# boardPower.net
KiCad netlist of a schematic drawn in Altium Designer
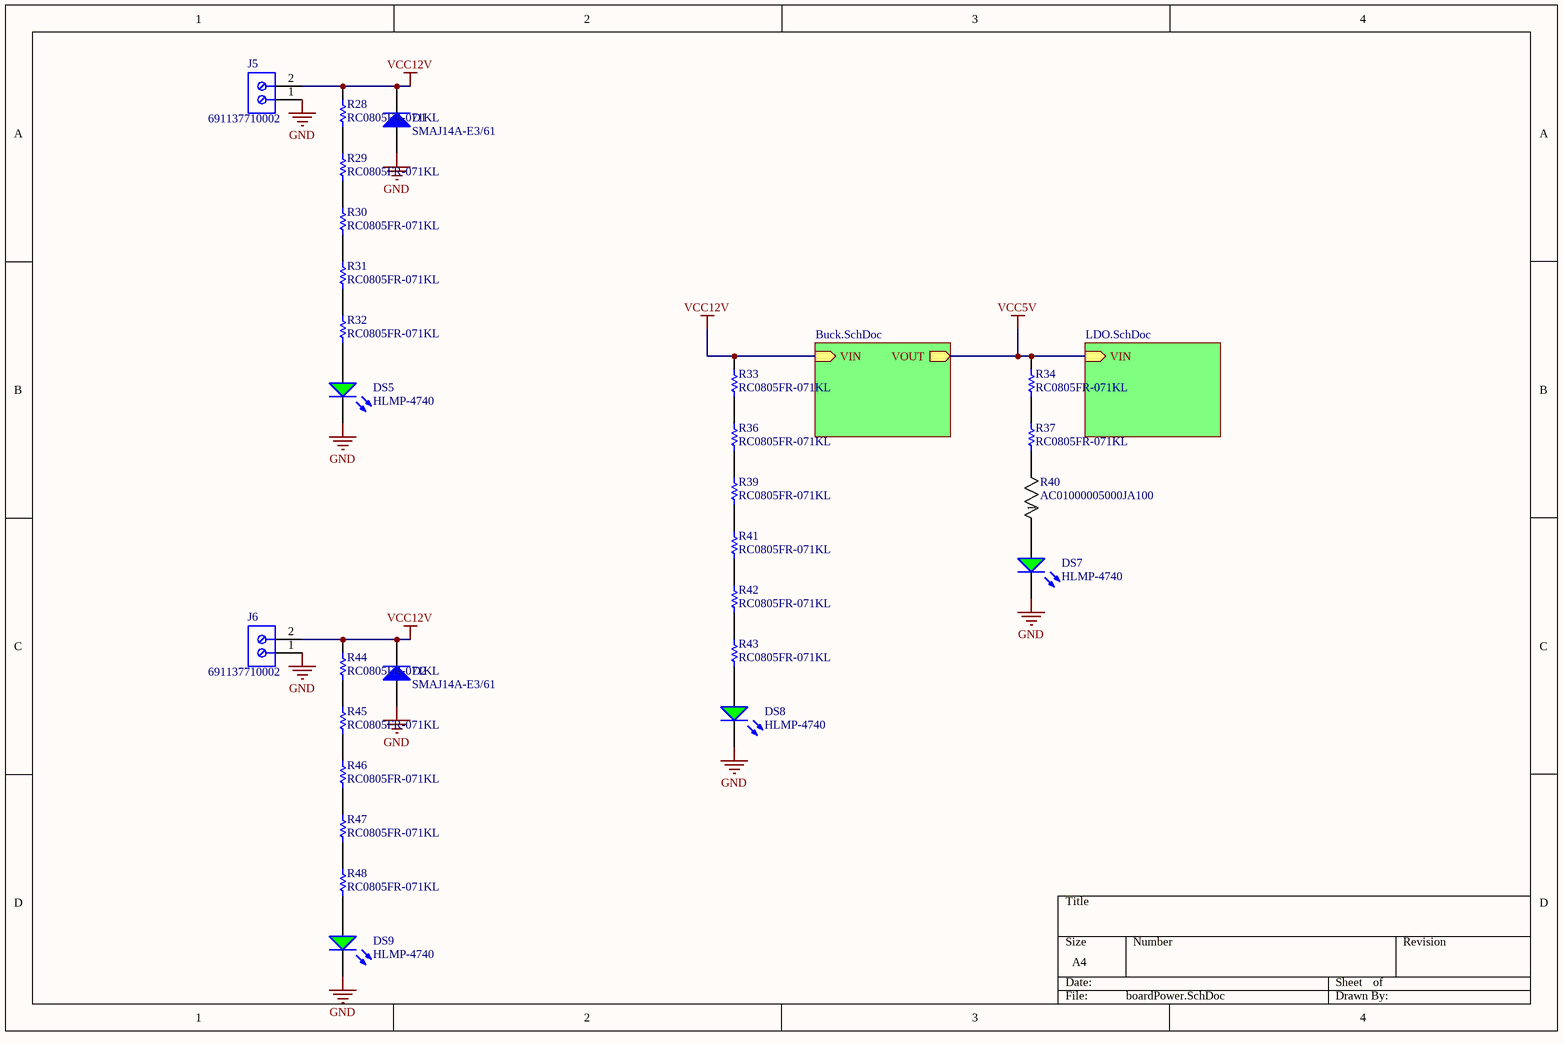
[diagram p0: boardPower.SchDoc]

(export (version "E")
  (design (tool "Eeschema 10.0.6"))
  (components
    (comp (ref "D1")
      (value "SMAJ14A-E3/61")
      (footprint "VISH-DO-214AC-2_L")
      (fields (field (name "MANUFACTURER") "Vishay Semiconductor"))
      (libsource (lib "Altium Content Vault") (part "VISH-K1A2-2"))
    )
    (comp (ref "D2")
      (value "SMAJ14A-E3/61")
      (footprint "VISH-DO-214AC-2_L")
      (fields (field (name "MANUFACTURER") "Vishay Semiconductor"))
      (libsource (lib "Altium Content Vault") (part "VISH-K1A2-2"))
    )
    (comp (ref "DS5")
      (value "HLMP-4740")
      (footprint "AVAG-HLMP-4740")
      (description "T-1 3/4 (5 mm) Low Current LED Lamp, Green, 1.9 V, -20 to 100 degC, 2-Pin THD, RoHS, Bulk")
      (fields (field (name "MANUFACTURER") "AvagoTechnologies"))
      (libsource (lib "Altium Content Vault") (part "LED-GREEN-AK-2"))
    )
    (comp (ref "DS7")
      (value "HLMP-4740")
      (footprint "AVAG-HLMP-4740")
      (description "T-1 3/4 (5 mm) Low Current LED Lamp, Green, 1.9 V, -20 to 100 degC, 2-Pin THD, RoHS, Bulk")
      (fields (field (name "MANUFACTURER") "AvagoTechnologies"))
      (libsource (lib "Altium Content Vault") (part "LED-GREEN-AK-2"))
    )
    (comp (ref "DS8")
      (value "HLMP-4740")
      (footprint "AVAG-HLMP-4740")
      (description "T-1 3/4 (5 mm) Low Current LED Lamp, Green, 1.9 V, -20 to 100 degC, 2-Pin THD, RoHS, Bulk")
      (fields (field (name "MANUFACTURER") "AvagoTechnologies"))
      (libsource (lib "Altium Content Vault") (part "LED-GREEN-AK-2"))
    )
    (comp (ref "DS9")
      (value "HLMP-4740")
      (footprint "AVAG-HLMP-4740")
      (description "T-1 3/4 (5 mm) Low Current LED Lamp, Green, 1.9 V, -20 to 100 degC, 2-Pin THD, RoHS, Bulk")
      (fields (field (name "MANUFACTURER") "AvagoTechnologies"))
      (libsource (lib "Altium Content Vault") (part "LED-GREEN-AK-2"))
    )
    (comp (ref "J5")
      (value "691137710002")
      (footprint "691137710002")
      (libsource (lib "Altium Content Vault") (part "TBL - 1R - 02P - Screw"))
    )
    (comp (ref "J6")
      (value "691137710002")
      (footprint "691137710002")
      (libsource (lib "Altium Content Vault") (part "TBL - 1R - 02P - Screw"))
    )
    (comp (ref "R28")
      (value "RC0805FR-071KL")
      (footprint "RESC2013X60X35ML10T20")
      (description "Chip Resistor, 1 KOhm, +/- 1%, 125 mW, -55 to 155 degC, 0805 (2012 Metric), RoHS, Tape and Reel")
      (fields (field (name "TOLERANCE") "1%") (field (name "MANUFACTURER") "Yageo"))
      (libsource (lib "Altium Content Vault") (part "RES-2"))
    )
    (comp (ref "R29")
      (value "RC0805FR-071KL")
      (footprint "RESC2013X60X35ML10T20")
      (description "Chip Resistor, 1 KOhm, +/- 1%, 125 mW, -55 to 155 degC, 0805 (2012 Metric), RoHS, Tape and Reel")
      (fields (field (name "TOLERANCE") "1%") (field (name "MANUFACTURER") "Yageo"))
      (libsource (lib "Altium Content Vault") (part "RES-2"))
    )
    (comp (ref "R30")
      (value "RC0805FR-071KL")
      (footprint "RESC2013X60X35ML10T20")
      (description "Chip Resistor, 1 KOhm, +/- 1%, 125 mW, -55 to 155 degC, 0805 (2012 Metric), RoHS, Tape and Reel")
      (fields (field (name "TOLERANCE") "1%") (field (name "MANUFACTURER") "Yageo"))
      (libsource (lib "Altium Content Vault") (part "RES-2"))
    )
    (comp (ref "R31")
      (value "RC0805FR-071KL")
      (footprint "RESC2013X60X35ML10T20")
      (description "Chip Resistor, 1 KOhm, +/- 1%, 125 mW, -55 to 155 degC, 0805 (2012 Metric), RoHS, Tape and Reel")
      (fields (field (name "TOLERANCE") "1%") (field (name "MANUFACTURER") "Yageo"))
      (libsource (lib "Altium Content Vault") (part "RES-2"))
    )
    (comp (ref "R32")
      (value "RC0805FR-071KL")
      (footprint "RESC2013X60X35ML10T20")
      (description "Chip Resistor, 1 KOhm, +/- 1%, 125 mW, -55 to 155 degC, 0805 (2012 Metric), RoHS, Tape and Reel")
      (fields (field (name "TOLERANCE") "1%") (field (name "MANUFACTURER") "Yageo"))
      (libsource (lib "Altium Content Vault") (part "RES-2"))
    )
    (comp (ref "R33")
      (value "RC0805FR-071KL")
      (footprint "RESC2013X60X35ML10T20")
      (description "Chip Resistor, 1 KOhm, +/- 1%, 125 mW, -55 to 155 degC, 0805 (2012 Metric), RoHS, Tape and Reel")
      (fields (field (name "TOLERANCE") "1%") (field (name "MANUFACTURER") "Yageo"))
      (libsource (lib "Altium Content Vault") (part "RES-2"))
    )
    (comp (ref "R34")
      (value "RC0805FR-071KL")
      (footprint "RESC2013X60X35ML10T20")
      (description "Chip Resistor, 1 KOhm, +/- 1%, 125 mW, -55 to 155 degC, 0805 (2012 Metric), RoHS, Tape and Reel")
      (fields (field (name "TOLERANCE") "1%") (field (name "MANUFACTURER") "Yageo"))
      (libsource (lib "Altium Content Vault") (part "RES-2"))
    )
    (comp (ref "R36")
      (value "RC0805FR-071KL")
      (footprint "RESC2013X60X35ML10T20")
      (description "Chip Resistor, 1 KOhm, +/- 1%, 125 mW, -55 to 155 degC, 0805 (2012 Metric), RoHS, Tape and Reel")
      (fields (field (name "TOLERANCE") "1%") (field (name "MANUFACTURER") "Yageo"))
      (libsource (lib "Altium Content Vault") (part "RES-2"))
    )
    (comp (ref "R37")
      (value "RC0805FR-071KL")
      (footprint "RESC2013X60X35ML10T20")
      (description "Chip Resistor, 1 KOhm, +/- 1%, 125 mW, -55 to 155 degC, 0805 (2012 Metric), RoHS, Tape and Reel")
      (fields (field (name "TOLERANCE") "1%") (field (name "MANUFACTURER") "Yageo"))
      (libsource (lib "Altium Content Vault") (part "RES-2"))
    )
    (comp (ref "R39")
      (value "RC0805FR-071KL")
      (footprint "RESC2013X60X35ML10T20")
      (description "Chip Resistor, 1 KOhm, +/- 1%, 125 mW, -55 to 155 degC, 0805 (2012 Metric), RoHS, Tape and Reel")
      (fields (field (name "TOLERANCE") "1%") (field (name "MANUFACTURER") "Yageo"))
      (libsource (lib "Altium Content Vault") (part "RES-2"))
    )
    (comp (ref "R40")
      (value "AC01000005000JA100")
      (footprint "RES_AC01_VIS")
      (fields (field (name "TOLERANCE") "5%"))
      (libsource (lib "Altium Content Vault") (part "AC01000005000JA100"))
    )
    (comp (ref "R41")
      (value "RC0805FR-071KL")
      (footprint "RESC2013X60X35ML10T20")
      (description "Chip Resistor, 1 KOhm, +/- 1%, 125 mW, -55 to 155 degC, 0805 (2012 Metric), RoHS, Tape and Reel")
      (fields (field (name "TOLERANCE") "1%") (field (name "MANUFACTURER") "Yageo"))
      (libsource (lib "Altium Content Vault") (part "RES-2"))
    )
    (comp (ref "R42")
      (value "RC0805FR-071KL")
      (footprint "RESC2013X60X35ML10T20")
      (description "Chip Resistor, 1 KOhm, +/- 1%, 125 mW, -55 to 155 degC, 0805 (2012 Metric), RoHS, Tape and Reel")
      (fields (field (name "TOLERANCE") "1%") (field (name "MANUFACTURER") "Yageo"))
      (libsource (lib "Altium Content Vault") (part "RES-2"))
    )
    (comp (ref "R43")
      (value "RC0805FR-071KL")
      (footprint "RESC2013X60X35ML10T20")
      (description "Chip Resistor, 1 KOhm, +/- 1%, 125 mW, -55 to 155 degC, 0805 (2012 Metric), RoHS, Tape and Reel")
      (fields (field (name "TOLERANCE") "1%") (field (name "MANUFACTURER") "Yageo"))
      (libsource (lib "Altium Content Vault") (part "RES-2"))
    )
    (comp (ref "R44")
      (value "RC0805FR-071KL")
      (footprint "RESC2013X60X35ML10T20")
      (description "Chip Resistor, 1 KOhm, +/- 1%, 125 mW, -55 to 155 degC, 0805 (2012 Metric), RoHS, Tape and Reel")
      (fields (field (name "TOLERANCE") "1%") (field (name "MANUFACTURER") "Yageo"))
      (libsource (lib "Altium Content Vault") (part "RES-2"))
    )
    (comp (ref "R45")
      (value "RC0805FR-071KL")
      (footprint "RESC2013X60X35ML10T20")
      (description "Chip Resistor, 1 KOhm, +/- 1%, 125 mW, -55 to 155 degC, 0805 (2012 Metric), RoHS, Tape and Reel")
      (fields (field (name "TOLERANCE") "1%") (field (name "MANUFACTURER") "Yageo"))
      (libsource (lib "Altium Content Vault") (part "RES-2"))
    )
    (comp (ref "R46")
      (value "RC0805FR-071KL")
      (footprint "RESC2013X60X35ML10T20")
      (description "Chip Resistor, 1 KOhm, +/- 1%, 125 mW, -55 to 155 degC, 0805 (2012 Metric), RoHS, Tape and Reel")
      (fields (field (name "TOLERANCE") "1%") (field (name "MANUFACTURER") "Yageo"))
      (libsource (lib "Altium Content Vault") (part "RES-2"))
    )
    (comp (ref "R47")
      (value "RC0805FR-071KL")
      (footprint "RESC2013X60X35ML10T20")
      (description "Chip Resistor, 1 KOhm, +/- 1%, 125 mW, -55 to 155 degC, 0805 (2012 Metric), RoHS, Tape and Reel")
      (fields (field (name "TOLERANCE") "1%") (field (name "MANUFACTURER") "Yageo"))
      (libsource (lib "Altium Content Vault") (part "RES-2"))
    )
    (comp (ref "R48")
      (value "RC0805FR-071KL")
      (footprint "RESC2013X60X35ML10T20")
      (description "Chip Resistor, 1 KOhm, +/- 1%, 125 mW, -55 to 155 degC, 0805 (2012 Metric), RoHS, Tape and Reel")
      (fields (field (name "TOLERANCE") "1%") (field (name "MANUFACTURER") "Yageo"))
      (libsource (lib "Altium Content Vault") (part "RES-2"))
    )
  )
  (nets
    (net (code "1") (name "GND") (class "Default")
      (node (ref "D1") (pin "2") (pinfunction "A_2") (pintype "passive"))
      (node (ref "D2") (pin "2") (pinfunction "A_2") (pintype "passive"))
      (node (ref "DS5") (pin "2") (pinfunction "K_2") (pintype "passive"))
      (node (ref "DS7") (pin "2") (pinfunction "K_2") (pintype "passive"))
      (node (ref "DS8") (pin "2") (pinfunction "K_2") (pintype "passive"))
      (node (ref "DS9") (pin "2") (pinfunction "K_2") (pintype "passive"))
      (node (ref "J5") (pin "1") (pinfunction "1_1") (pintype "passive"))
      (node (ref "J6") (pin "1") (pinfunction "1_1") (pintype "passive"))
    )
    (net (code "2") (name "Net-(DS5-A)") (class "Default")
      (node (ref "DS5") (pin "1") (pinfunction "A_1") (pintype "passive"))
      (node (ref "R32") (pin "1") (pinfunction "1_1") (pintype "passive"))
    )
    (net (code "3") (name "Net-(DS7-A)") (class "Default")
      (node (ref "DS7") (pin "1") (pinfunction "A_1") (pintype "passive"))
      (node (ref "R40") (pin "1") (pinfunction "1_1") (pintype "passive"))
    )
    (net (code "4") (name "Net-(DS8-A)") (class "Default")
      (node (ref "DS8") (pin "1") (pinfunction "A_1") (pintype "passive"))
      (node (ref "R43") (pin "1") (pinfunction "1_1") (pintype "passive"))
    )
    (net (code "5") (name "Net-(DS9-A)") (class "Default")
      (node (ref "DS9") (pin "1") (pinfunction "A_1") (pintype "passive"))
      (node (ref "R48") (pin "1") (pinfunction "1_1") (pintype "passive"))
    )
    (net (code "6") (name "Net-(R28-Pad1)") (class "Default")
      (node (ref "R28") (pin "1") (pinfunction "1_1") (pintype "passive"))
      (node (ref "R29") (pin "2") (pinfunction "2_2") (pintype "passive"))
    )
    (net (code "7") (name "Net-(R29-Pad1)") (class "Default")
      (node (ref "R29") (pin "1") (pinfunction "1_1") (pintype "passive"))
      (node (ref "R30") (pin "2") (pinfunction "2_2") (pintype "passive"))
    )
    (net (code "8") (name "Net-(R30-Pad1)") (class "Default")
      (node (ref "R30") (pin "1") (pinfunction "1_1") (pintype "passive"))
      (node (ref "R31") (pin "2") (pinfunction "2_2") (pintype "passive"))
    )
    (net (code "9") (name "Net-(R31-Pad1)") (class "Default")
      (node (ref "R31") (pin "1") (pinfunction "1_1") (pintype "passive"))
      (node (ref "R32") (pin "2") (pinfunction "2_2") (pintype "passive"))
    )
    (net (code "10") (name "Net-(R33-Pad1)") (class "Default")
      (node (ref "R33") (pin "1") (pinfunction "1_1") (pintype "passive"))
      (node (ref "R36") (pin "2") (pinfunction "2_2") (pintype "passive"))
    )
    (net (code "11") (name "Net-(R34-Pad1)") (class "Default")
      (node (ref "R34") (pin "1") (pinfunction "1_1") (pintype "passive"))
      (node (ref "R37") (pin "2") (pinfunction "2_2") (pintype "passive"))
    )
    (net (code "12") (name "Net-(R36-Pad1)") (class "Default")
      (node (ref "R36") (pin "1") (pinfunction "1_1") (pintype "passive"))
      (node (ref "R39") (pin "2") (pinfunction "2_2") (pintype "passive"))
    )
    (net (code "13") (name "Net-(R37-Pad1)") (class "Default")
      (node (ref "R37") (pin "1") (pinfunction "1_1") (pintype "passive"))
      (node (ref "R40") (pin "2") (pinfunction "2_2") (pintype "passive"))
    )
    (net (code "14") (name "Net-(R39-Pad1)") (class "Default")
      (node (ref "R39") (pin "1") (pinfunction "1_1") (pintype "passive"))
      (node (ref "R41") (pin "2") (pinfunction "2_2") (pintype "passive"))
    )
    (net (code "15") (name "Net-(R41-Pad1)") (class "Default")
      (node (ref "R41") (pin "1") (pinfunction "1_1") (pintype "passive"))
      (node (ref "R42") (pin "2") (pinfunction "2_2") (pintype "passive"))
    )
    (net (code "16") (name "Net-(R42-Pad1)") (class "Default")
      (node (ref "R42") (pin "1") (pinfunction "1_1") (pintype "passive"))
      (node (ref "R43") (pin "2") (pinfunction "2_2") (pintype "passive"))
    )
    (net (code "17") (name "Net-(R44-Pad1)") (class "Default")
      (node (ref "R44") (pin "1") (pinfunction "1_1") (pintype "passive"))
      (node (ref "R45") (pin "2") (pinfunction "2_2") (pintype "passive"))
    )
    (net (code "18") (name "Net-(R45-Pad1)") (class "Default")
      (node (ref "R45") (pin "1") (pinfunction "1_1") (pintype "passive"))
      (node (ref "R46") (pin "2") (pinfunction "2_2") (pintype "passive"))
    )
    (net (code "19") (name "Net-(R46-Pad1)") (class "Default")
      (node (ref "R46") (pin "1") (pinfunction "1_1") (pintype "passive"))
      (node (ref "R47") (pin "2") (pinfunction "2_2") (pintype "passive"))
    )
    (net (code "20") (name "Net-(R47-Pad1)") (class "Default")
      (node (ref "R47") (pin "1") (pinfunction "1_1") (pintype "passive"))
      (node (ref "R48") (pin "2") (pinfunction "2_2") (pintype "passive"))
    )
    (net (code "21") (name "VCC5V") (class "Default")
      (node (ref "R34") (pin "2") (pinfunction "2_2") (pintype "passive"))
    )
    (net (code "22") (name "VCC12V") (class "Default")
      (node (ref "D1") (pin "1") (pinfunction "K_1") (pintype "passive"))
      (node (ref "D2") (pin "1") (pinfunction "K_1") (pintype "passive"))
      (node (ref "J5") (pin "2") (pinfunction "2_2") (pintype "passive"))
      (node (ref "J6") (pin "2") (pinfunction "2_2") (pintype "passive"))
      (node (ref "R28") (pin "2") (pinfunction "2_2") (pintype "passive"))
      (node (ref "R33") (pin "2") (pinfunction "2_2") (pintype "passive"))
      (node (ref "R44") (pin "2") (pinfunction "2_2") (pintype "passive"))
    )
  )
)
